# BeatleCalc.net
KiCad netlist of a schematic drawn in EAGLE
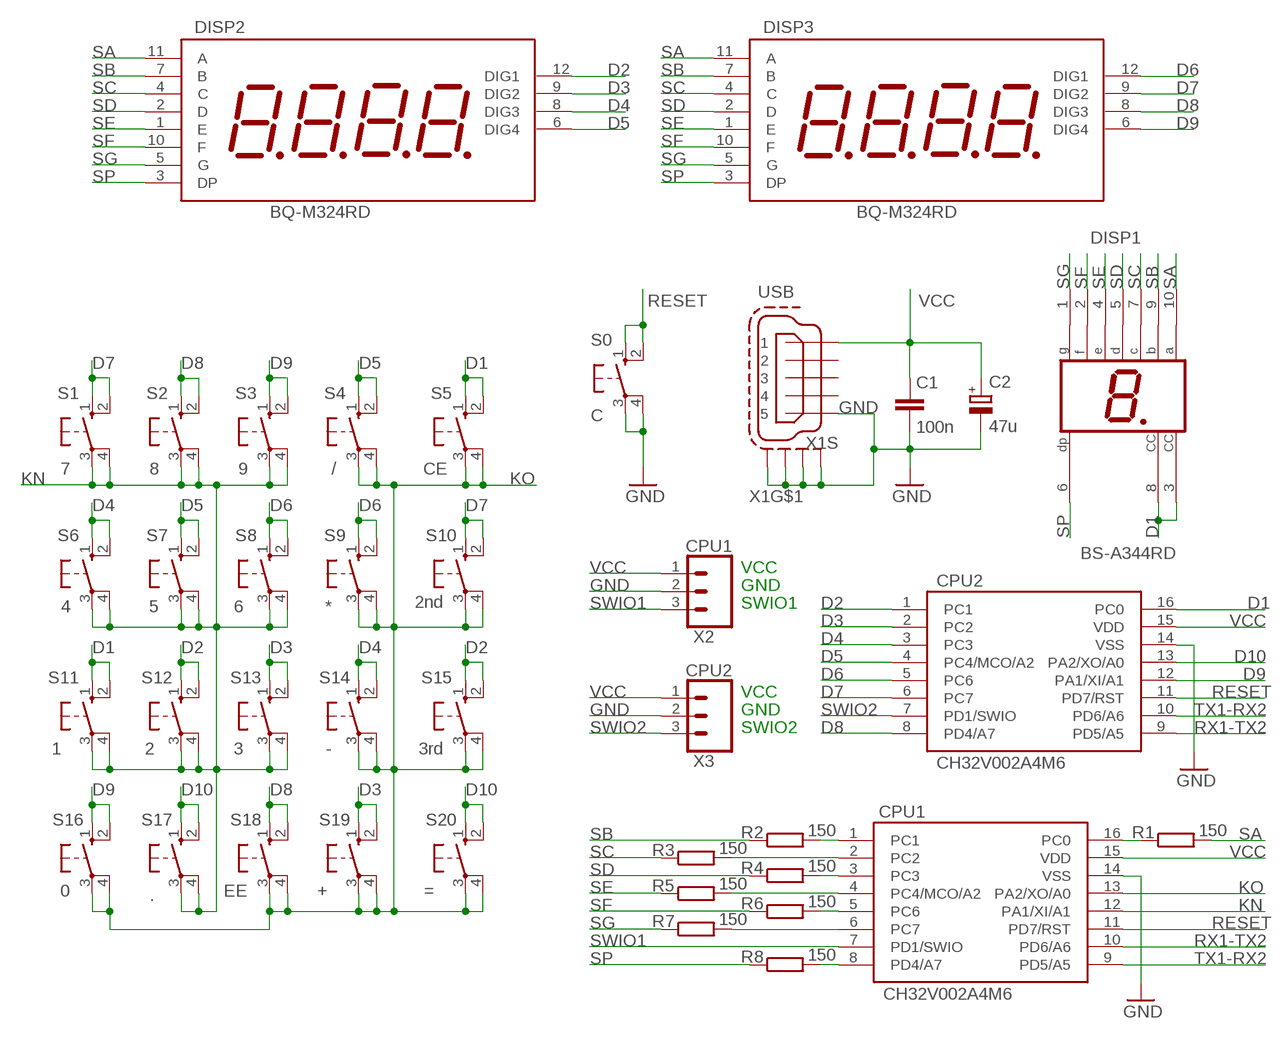
[diagram p0: schematic, sheet 1]

(export (version "E")
  (design (tool "Eeschema 10.0.6"))
  (components
    (comp (ref "C1")
      (value "100n")
      (footprint "eagle-import:C050-024X044")
      (libsource (lib "eagle-import") (part "C-EU050-024X044"))
    )
    (comp (ref "C2")
      (value "47u")
      (footprint "eagle-import:TT2D6L")
      (libsource (lib "eagle-import") (part "CPOL-EUTT2D6L"))
    )
    (comp (ref "CPU1")
      (value "CH32V002A4M6")
      (footprint "eagle-import:SOP16")
      (libsource (lib "eagle-import") (part "CH32V002A4M6"))
    )
    (comp (ref "CPU2")
      (value "CH32V002A4M6")
      (footprint "eagle-import:SOP16")
      (libsource (lib "eagle-import") (part "CH32V002A4M6"))
    )
    (comp (ref "DISP1")
      (value "BS-A344RD")
      (footprint "eagle-import:HDSP-E")
      (libsource (lib "eagle-import") (part "SC39-11SRWA"))
    )
    (comp (ref "DISP2")
      (value "BQ-M324RD")
      (footprint "eagle-import:4DIG_7SEG_92MM")
      (libsource (lib "eagle-import") (part "4DIG_7SEG_92MM"))
    )
    (comp (ref "DISP3")
      (value "BQ-M324RD")
      (footprint "eagle-import:4DIG_7SEG_92MM")
      (libsource (lib "eagle-import") (part "4DIG_7SEG_92MM"))
    )
    (comp (ref "R1")
      (value "150")
      (footprint "eagle-import:0204_10")
      (libsource (lib "eagle-import") (part "R-EU_0204/10"))
    )
    (comp (ref "R2")
      (value "150")
      (footprint "eagle-import:0204_10")
      (libsource (lib "eagle-import") (part "R-EU_0204/10"))
    )
    (comp (ref "R3")
      (value "150")
      (footprint "eagle-import:0204_10")
      (libsource (lib "eagle-import") (part "R-EU_0204/10"))
    )
    (comp (ref "R4")
      (value "150")
      (footprint "eagle-import:0204_10")
      (libsource (lib "eagle-import") (part "R-EU_0204/10"))
    )
    (comp (ref "R5")
      (value "150")
      (footprint "eagle-import:0204_10")
      (libsource (lib "eagle-import") (part "R-EU_0204/10"))
    )
    (comp (ref "R6")
      (value "150")
      (footprint "eagle-import:0204_10")
      (libsource (lib "eagle-import") (part "R-EU_0204/10"))
    )
    (comp (ref "R7")
      (value "150")
      (footprint "eagle-import:0204_10")
      (libsource (lib "eagle-import") (part "R-EU_0204/10"))
    )
    (comp (ref "R8")
      (value "150")
      (footprint "eagle-import:0204_10")
      (libsource (lib "eagle-import") (part "R-EU_0204/10"))
    )
    (comp (ref "S0")
      (value "C")
      (footprint "eagle-import:B3F-10XX")
      (fields (field (name "MPN") "B3F-1000"))
      (libsource (lib "eagle-import") (part "10-XX"))
    )
    (comp (ref "S1")
      (value "7")
      (footprint "eagle-import:B3F-10XX")
      (fields (field (name "MPN") "B3F-1000"))
      (libsource (lib "eagle-import") (part "10-XX"))
    )
    (comp (ref "S2")
      (value "8")
      (footprint "eagle-import:B3F-10XX")
      (fields (field (name "MPN") "B3F-1000"))
      (libsource (lib "eagle-import") (part "10-XX"))
    )
    (comp (ref "S3")
      (value "9")
      (footprint "eagle-import:B3F-10XX")
      (fields (field (name "MPN") "B3F-1000"))
      (libsource (lib "eagle-import") (part "10-XX"))
    )
    (comp (ref "S4")
      (value "/")
      (footprint "eagle-import:B3F-10XX")
      (fields (field (name "MPN") "B3F-1000"))
      (libsource (lib "eagle-import") (part "10-XX"))
    )
    (comp (ref "S5")
      (value "CE")
      (footprint "eagle-import:B3F-10XX")
      (fields (field (name "MPN") "B3F-1000"))
      (libsource (lib "eagle-import") (part "10-XX"))
    )
    (comp (ref "S6")
      (value "4")
      (footprint "eagle-import:B3F-10XX")
      (fields (field (name "MPN") "B3F-1000"))
      (libsource (lib "eagle-import") (part "10-XX"))
    )
    (comp (ref "S7")
      (value "5")
      (footprint "eagle-import:B3F-10XX")
      (fields (field (name "MPN") "B3F-1000"))
      (libsource (lib "eagle-import") (part "10-XX"))
    )
    (comp (ref "S8")
      (value "6")
      (footprint "eagle-import:B3F-10XX")
      (fields (field (name "MPN") "B3F-1000"))
      (libsource (lib "eagle-import") (part "10-XX"))
    )
    (comp (ref "S9")
      (value "*")
      (footprint "eagle-import:B3F-10XX")
      (fields (field (name "MPN") "B3F-1000"))
      (libsource (lib "eagle-import") (part "10-XX"))
    )
    (comp (ref "S10")
      (value "2nd")
      (footprint "eagle-import:B3F-10XX")
      (fields (field (name "MPN") "B3F-1000"))
      (libsource (lib "eagle-import") (part "10-XX"))
    )
    (comp (ref "S11")
      (value "1")
      (footprint "eagle-import:B3F-10XX")
      (fields (field (name "MPN") "B3F-1000"))
      (libsource (lib "eagle-import") (part "10-XX"))
    )
    (comp (ref "S12")
      (value "2")
      (footprint "eagle-import:B3F-10XX")
      (fields (field (name "MPN") "B3F-1000"))
      (libsource (lib "eagle-import") (part "10-XX"))
    )
    (comp (ref "S13")
      (value "3")
      (footprint "eagle-import:B3F-10XX")
      (fields (field (name "MPN") "B3F-1000"))
      (libsource (lib "eagle-import") (part "10-XX"))
    )
    (comp (ref "S14")
      (value "-")
      (footprint "eagle-import:B3F-10XX")
      (fields (field (name "MPN") "B3F-1000"))
      (libsource (lib "eagle-import") (part "10-XX"))
    )
    (comp (ref "S15")
      (value "3rd")
      (footprint "eagle-import:B3F-10XX")
      (fields (field (name "MPN") "B3F-1000"))
      (libsource (lib "eagle-import") (part "10-XX"))
    )
    (comp (ref "S16")
      (value "0")
      (footprint "eagle-import:B3F-10XX")
      (fields (field (name "MPN") "B3F-1000"))
      (libsource (lib "eagle-import") (part "10-XX"))
    )
    (comp (ref "S17")
      (value ".")
      (footprint "eagle-import:B3F-10XX")
      (fields (field (name "MPN") "B3F-1000"))
      (libsource (lib "eagle-import") (part "10-XX"))
    )
    (comp (ref "S18")
      (value "EE")
      (footprint "eagle-import:B3F-10XX")
      (fields (field (name "MPN") "B3F-1000"))
      (libsource (lib "eagle-import") (part "10-XX"))
    )
    (comp (ref "S19")
      (value "+")
      (footprint "eagle-import:B3F-10XX")
      (fields (field (name "MPN") "B3F-1000"))
      (libsource (lib "eagle-import") (part "10-XX"))
    )
    (comp (ref "S20")
      (value "=")
      (footprint "eagle-import:B3F-10XX")
      (fields (field (name "MPN") "B3F-1000"))
      (libsource (lib "eagle-import") (part "10-XX"))
    )
    (comp (ref "X1")
      (value "USB")
      (footprint "eagle-import:32005-201")
      (libsource (lib "eagle-import") (part "MINI-USB-SCHIELD-32005-201"))
    )
    (comp (ref "X2")
      (value "CPU1")
      (footprint "eagle-import:1X03_LONGPADS")
      (libsource (lib "eagle-import") (part "CONN_03LONGPADS"))
    )
    (comp (ref "X3")
      (value "CPU2")
      (footprint "eagle-import:1X03_LONGPADS")
      (libsource (lib "eagle-import") (part "CONN_03LONGPADS"))
    )
  )
  (nets
    (net (code "1") (name "/D1") (class "Default")
      (node (ref "CPU2") (pin "16") (pinfunction "PC0_16") (pintype "bidirectional"))
      (node (ref "DISP1") (pin "3") (pinfunction "CC_3") (pintype "passive"))
      (node (ref "DISP1") (pin "8") (pinfunction "CC_8") (pintype "passive"))
      (node (ref "S11") (pin "1") (pinfunction "S_1") (pintype "passive"))
      (node (ref "S11") (pin "2") (pinfunction "S1_2") (pintype "passive"))
      (node (ref "S5") (pin "1") (pinfunction "S_1") (pintype "passive"))
      (node (ref "S5") (pin "2") (pinfunction "S1_2") (pintype "passive"))
    )
    (net (code "2") (name "/D2") (class "Default")
      (node (ref "CPU2") (pin "1") (pinfunction "PC1_1") (pintype "bidirectional"))
      (node (ref "DISP2") (pin "12") (pinfunction "DIG1_12") (pintype "bidirectional"))
      (node (ref "S12") (pin "1") (pinfunction "S_1") (pintype "passive"))
      (node (ref "S12") (pin "2") (pinfunction "S1_2") (pintype "passive"))
      (node (ref "S15") (pin "1") (pinfunction "S_1") (pintype "passive"))
      (node (ref "S15") (pin "2") (pinfunction "S1_2") (pintype "passive"))
    )
    (net (code "3") (name "/D3") (class "Default")
      (node (ref "CPU2") (pin "2") (pinfunction "PC2_2") (pintype "bidirectional"))
      (node (ref "DISP2") (pin "9") (pinfunction "DIG2_9") (pintype "bidirectional"))
      (node (ref "S13") (pin "1") (pinfunction "S_1") (pintype "passive"))
      (node (ref "S13") (pin "2") (pinfunction "S1_2") (pintype "passive"))
      (node (ref "S19") (pin "1") (pinfunction "S_1") (pintype "passive"))
      (node (ref "S19") (pin "2") (pinfunction "S1_2") (pintype "passive"))
    )
    (net (code "4") (name "/D4") (class "Default")
      (node (ref "CPU2") (pin "3") (pinfunction "PC3_3") (pintype "bidirectional"))
      (node (ref "DISP2") (pin "8") (pinfunction "DIG3_8") (pintype "bidirectional"))
      (node (ref "S14") (pin "1") (pinfunction "S_1") (pintype "passive"))
      (node (ref "S14") (pin "2") (pinfunction "S1_2") (pintype "passive"))
      (node (ref "S6") (pin "1") (pinfunction "S_1") (pintype "passive"))
      (node (ref "S6") (pin "2") (pinfunction "S1_2") (pintype "passive"))
    )
    (net (code "5") (name "/D5") (class "Default")
      (node (ref "CPU2") (pin "4") (pinfunction "PC4/MCO/A2_4") (pintype "bidirectional"))
      (node (ref "DISP2") (pin "6") (pinfunction "DIG4_6") (pintype "bidirectional"))
      (node (ref "S4") (pin "1") (pinfunction "S_1") (pintype "passive"))
      (node (ref "S4") (pin "2") (pinfunction "S1_2") (pintype "passive"))
      (node (ref "S7") (pin "1") (pinfunction "S_1") (pintype "passive"))
      (node (ref "S7") (pin "2") (pinfunction "S1_2") (pintype "passive"))
    )
    (net (code "6") (name "/D6") (class "Default")
      (node (ref "CPU2") (pin "5") (pinfunction "PC6_5") (pintype "bidirectional"))
      (node (ref "DISP3") (pin "12") (pinfunction "DIG1_12") (pintype "bidirectional"))
      (node (ref "S8") (pin "1") (pinfunction "S_1") (pintype "passive"))
      (node (ref "S8") (pin "2") (pinfunction "S1_2") (pintype "passive"))
      (node (ref "S9") (pin "1") (pinfunction "S_1") (pintype "passive"))
      (node (ref "S9") (pin "2") (pinfunction "S1_2") (pintype "passive"))
    )
    (net (code "7") (name "/D7") (class "Default")
      (node (ref "CPU2") (pin "6") (pinfunction "PC7_6") (pintype "bidirectional"))
      (node (ref "DISP3") (pin "9") (pinfunction "DIG2_9") (pintype "bidirectional"))
      (node (ref "S1") (pin "1") (pinfunction "S_1") (pintype "passive"))
      (node (ref "S1") (pin "2") (pinfunction "S1_2") (pintype "passive"))
      (node (ref "S10") (pin "1") (pinfunction "S_1") (pintype "passive"))
      (node (ref "S10") (pin "2") (pinfunction "S1_2") (pintype "passive"))
    )
    (net (code "8") (name "/D8") (class "Default")
      (node (ref "CPU2") (pin "8") (pinfunction "PD4/A7_8") (pintype "bidirectional"))
      (node (ref "DISP3") (pin "8") (pinfunction "DIG3_8") (pintype "bidirectional"))
      (node (ref "S18") (pin "1") (pinfunction "S_1") (pintype "passive"))
      (node (ref "S18") (pin "2") (pinfunction "S1_2") (pintype "passive"))
      (node (ref "S2") (pin "1") (pinfunction "S_1") (pintype "passive"))
      (node (ref "S2") (pin "2") (pinfunction "S1_2") (pintype "passive"))
    )
    (net (code "9") (name "/D9") (class "Default")
      (node (ref "CPU2") (pin "12") (pinfunction "PA1/XI/A1_12") (pintype "bidirectional"))
      (node (ref "DISP3") (pin "6") (pinfunction "DIG4_6") (pintype "bidirectional"))
      (node (ref "S16") (pin "1") (pinfunction "S_1") (pintype "passive"))
      (node (ref "S16") (pin "2") (pinfunction "S1_2") (pintype "passive"))
      (node (ref "S3") (pin "1") (pinfunction "S_1") (pintype "passive"))
      (node (ref "S3") (pin "2") (pinfunction "S1_2") (pintype "passive"))
    )
    (net (code "10") (name "/D10") (class "Default")
      (node (ref "CPU2") (pin "13") (pinfunction "PA2/XO/A0_13") (pintype "bidirectional"))
      (node (ref "S17") (pin "1") (pinfunction "S_1") (pintype "passive"))
      (node (ref "S17") (pin "2") (pinfunction "S1_2") (pintype "passive"))
      (node (ref "S20") (pin "1") (pinfunction "S_1") (pintype "passive"))
      (node (ref "S20") (pin "2") (pinfunction "S1_2") (pintype "passive"))
    )
    (net (code "11") (name "/KN") (class "Default")
      (node (ref "CPU1") (pin "12") (pinfunction "PA1/XI/A1_12") (pintype "bidirectional"))
      (node (ref "S1") (pin "3") (pinfunction "P_3") (pintype "passive"))
      (node (ref "S1") (pin "4") (pinfunction "P1_4") (pintype "passive"))
      (node (ref "S11") (pin "3") (pinfunction "P_3") (pintype "passive"))
      (node (ref "S11") (pin "4") (pinfunction "P1_4") (pintype "passive"))
      (node (ref "S12") (pin "3") (pinfunction "P_3") (pintype "passive"))
      (node (ref "S12") (pin "4") (pinfunction "P1_4") (pintype "passive"))
      (node (ref "S13") (pin "3") (pinfunction "P_3") (pintype "passive"))
      (node (ref "S13") (pin "4") (pinfunction "P1_4") (pintype "passive"))
      (node (ref "S17") (pin "3") (pinfunction "P_3") (pintype "passive"))
      (node (ref "S17") (pin "4") (pinfunction "P1_4") (pintype "passive"))
      (node (ref "S2") (pin "3") (pinfunction "P_3") (pintype "passive"))
      (node (ref "S2") (pin "4") (pinfunction "P1_4") (pintype "passive"))
      (node (ref "S3") (pin "3") (pinfunction "P_3") (pintype "passive"))
      (node (ref "S3") (pin "4") (pinfunction "P1_4") (pintype "passive"))
      (node (ref "S6") (pin "3") (pinfunction "P_3") (pintype "passive"))
      (node (ref "S6") (pin "4") (pinfunction "P1_4") (pintype "passive"))
      (node (ref "S7") (pin "3") (pinfunction "P_3") (pintype "passive"))
      (node (ref "S7") (pin "4") (pinfunction "P1_4") (pintype "passive"))
      (node (ref "S8") (pin "3") (pinfunction "P_3") (pintype "passive"))
      (node (ref "S8") (pin "4") (pinfunction "P1_4") (pintype "passive"))
    )
    (net (code "12") (name "/KO") (class "Default")
      (node (ref "CPU1") (pin "13") (pinfunction "PA2/XO/A0_13") (pintype "bidirectional"))
      (node (ref "S10") (pin "3") (pinfunction "P_3") (pintype "passive"))
      (node (ref "S10") (pin "4") (pinfunction "P1_4") (pintype "passive"))
      (node (ref "S14") (pin "3") (pinfunction "P_3") (pintype "passive"))
      (node (ref "S14") (pin "4") (pinfunction "P1_4") (pintype "passive"))
      (node (ref "S15") (pin "3") (pinfunction "P_3") (pintype "passive"))
      (node (ref "S15") (pin "4") (pinfunction "P1_4") (pintype "passive"))
      (node (ref "S16") (pin "3") (pinfunction "P_3") (pintype "passive"))
      (node (ref "S16") (pin "4") (pinfunction "P1_4") (pintype "passive"))
      (node (ref "S18") (pin "3") (pinfunction "P_3") (pintype "passive"))
      (node (ref "S18") (pin "4") (pinfunction "P1_4") (pintype "passive"))
      (node (ref "S19") (pin "3") (pinfunction "P_3") (pintype "passive"))
      (node (ref "S19") (pin "4") (pinfunction "P1_4") (pintype "passive"))
      (node (ref "S20") (pin "3") (pinfunction "P_3") (pintype "passive"))
      (node (ref "S20") (pin "4") (pinfunction "P1_4") (pintype "passive"))
      (node (ref "S4") (pin "3") (pinfunction "P_3") (pintype "passive"))
      (node (ref "S4") (pin "4") (pinfunction "P1_4") (pintype "passive"))
      (node (ref "S5") (pin "3") (pinfunction "P_3") (pintype "passive"))
      (node (ref "S5") (pin "4") (pinfunction "P1_4") (pintype "passive"))
      (node (ref "S9") (pin "3") (pinfunction "P_3") (pintype "passive"))
      (node (ref "S9") (pin "4") (pinfunction "P1_4") (pintype "passive"))
    )
    (net (code "13") (name "/RESET") (class "Default")
      (node (ref "CPU1") (pin "11") (pinfunction "PD7/RST_11") (pintype "bidirectional"))
      (node (ref "CPU2") (pin "11") (pinfunction "PD7/RST_11") (pintype "bidirectional"))
      (node (ref "S0") (pin "1") (pinfunction "S_1") (pintype "passive"))
      (node (ref "S0") (pin "2") (pinfunction "S1_2") (pintype "passive"))
    )
    (net (code "14") (name "/RX1-TX2") (class "Default")
      (node (ref "CPU1") (pin "10") (pinfunction "PD6/A6_10") (pintype "bidirectional"))
      (node (ref "CPU2") (pin "9") (pinfunction "PD5/A5_9") (pintype "bidirectional"))
    )
    (net (code "15") (name "/SA") (class "Default")
      (node (ref "DISP1") (pin "10") (pinfunction "A_10") (pintype "passive"))
      (node (ref "DISP2") (pin "11") (pinfunction "A_11") (pintype "bidirectional"))
      (node (ref "DISP3") (pin "11") (pinfunction "A_11") (pintype "bidirectional"))
      (node (ref "R1") (pin "2") (pinfunction "2_2") (pintype "passive"))
    )
    (net (code "16") (name "/SB") (class "Default")
      (node (ref "DISP1") (pin "9") (pinfunction "B_9") (pintype "passive"))
      (node (ref "DISP2") (pin "7") (pinfunction "B_7") (pintype "bidirectional"))
      (node (ref "DISP3") (pin "7") (pinfunction "B_7") (pintype "bidirectional"))
      (node (ref "R2") (pin "1") (pinfunction "1_1") (pintype "passive"))
    )
    (net (code "17") (name "/SC") (class "Default")
      (node (ref "DISP1") (pin "7") (pinfunction "C_7") (pintype "passive"))
      (node (ref "DISP2") (pin "4") (pinfunction "C_4") (pintype "bidirectional"))
      (node (ref "DISP3") (pin "4") (pinfunction "C_4") (pintype "bidirectional"))
      (node (ref "R3") (pin "1") (pinfunction "1_1") (pintype "passive"))
    )
    (net (code "18") (name "/SD") (class "Default")
      (node (ref "DISP1") (pin "5") (pinfunction "D_5") (pintype "passive"))
      (node (ref "DISP2") (pin "2") (pinfunction "D_2") (pintype "bidirectional"))
      (node (ref "DISP3") (pin "2") (pinfunction "D_2") (pintype "bidirectional"))
      (node (ref "R4") (pin "1") (pinfunction "1_1") (pintype "passive"))
    )
    (net (code "19") (name "/SE") (class "Default")
      (node (ref "DISP1") (pin "4") (pinfunction "E_4") (pintype "passive"))
      (node (ref "DISP2") (pin "1") (pinfunction "E_1") (pintype "bidirectional"))
      (node (ref "DISP3") (pin "1") (pinfunction "E_1") (pintype "bidirectional"))
      (node (ref "R5") (pin "1") (pinfunction "1_1") (pintype "passive"))
    )
    (net (code "20") (name "/SF") (class "Default")
      (node (ref "DISP1") (pin "2") (pinfunction "F_2") (pintype "passive"))
      (node (ref "DISP2") (pin "10") (pinfunction "F_10") (pintype "bidirectional"))
      (node (ref "DISP3") (pin "10") (pinfunction "F_10") (pintype "bidirectional"))
      (node (ref "R6") (pin "1") (pinfunction "1_1") (pintype "passive"))
    )
    (net (code "21") (name "/SG") (class "Default")
      (node (ref "DISP1") (pin "1") (pinfunction "G_1") (pintype "passive"))
      (node (ref "DISP2") (pin "5") (pinfunction "G_5") (pintype "bidirectional"))
      (node (ref "DISP3") (pin "5") (pinfunction "G_5") (pintype "bidirectional"))
      (node (ref "R7") (pin "1") (pinfunction "1_1") (pintype "passive"))
    )
    (net (code "22") (name "/SP") (class "Default")
      (node (ref "DISP1") (pin "6") (pinfunction "DP_6") (pintype "passive"))
      (node (ref "DISP2") (pin "3") (pinfunction "DP_3") (pintype "bidirectional"))
      (node (ref "DISP3") (pin "3") (pinfunction "DP_3") (pintype "bidirectional"))
      (node (ref "R8") (pin "1") (pinfunction "1_1") (pintype "passive"))
    )
    (net (code "23") (name "/SWIO1") (class "Default")
      (node (ref "CPU1") (pin "7") (pinfunction "PD1/SWIO_7") (pintype "bidirectional"))
      (node (ref "X2") (pin "3") (pinfunction "3_3") (pintype "passive"))
    )
    (net (code "24") (name "/SWIO2") (class "Default")
      (node (ref "CPU2") (pin "7") (pinfunction "PD1/SWIO_7") (pintype "bidirectional"))
      (node (ref "X3") (pin "3") (pinfunction "3_3") (pintype "passive"))
    )
    (net (code "25") (name "/TX1-RX2") (class "Default")
      (node (ref "CPU1") (pin "9") (pinfunction "PD5/A5_9") (pintype "bidirectional"))
      (node (ref "CPU2") (pin "10") (pinfunction "PD6/A6_10") (pintype "bidirectional"))
    )
    (net (code "26") (name "/VCC") (class "Default")
      (node (ref "C1") (pin "1") (pinfunction "1_1") (pintype "passive"))
      (node (ref "C2") (pin "+") (pinfunction "+_+") (pintype "passive"))
      (node (ref "CPU1") (pin "15") (pinfunction "VDD_15") (pintype "power_in"))
      (node (ref "CPU2") (pin "15") (pinfunction "VDD_15") (pintype "power_in"))
      (node (ref "X1") (pin "1") (pinfunction "1_1") (pintype "passive"))
      (node (ref "X2") (pin "1") (pinfunction "1_1") (pintype "passive"))
      (node (ref "X3") (pin "1") (pinfunction "1_1") (pintype "passive"))
    )
    (net (code "27") (name "GND") (class "Default")
      (node (ref "C1") (pin "2") (pinfunction "2_2") (pintype "passive"))
      (node (ref "C2") (pin "-") (pinfunction "-_-") (pintype "passive"))
      (node (ref "CPU1") (pin "14") (pinfunction "VSS_14") (pintype "power_in"))
      (node (ref "CPU2") (pin "14") (pinfunction "VSS_14") (pintype "power_in"))
      (node (ref "S0") (pin "3") (pinfunction "P_3") (pintype "passive"))
      (node (ref "S0") (pin "4") (pinfunction "P1_4") (pintype "passive"))
      (node (ref "X1") (pin "5") (pinfunction "5_5") (pintype "passive"))
      (node (ref "X1") (pin "M1") (pinfunction "S1_M1") (pintype "passive"))
      (node (ref "X1") (pin "M2") (pinfunction "S2_M2") (pintype "passive"))
      (node (ref "X1") (pin "M3") (pinfunction "S3_M3") (pintype "passive"))
      (node (ref "X1") (pin "M4") (pinfunction "S4_M4") (pintype "passive"))
      (node (ref "X2") (pin "2") (pinfunction "2_2") (pintype "passive"))
      (node (ref "X3") (pin "2") (pinfunction "2_2") (pintype "passive"))
    )
    (net (code "28") (name "Net-(CPU1-PC0)") (class "Default")
      (node (ref "CPU1") (pin "16") (pinfunction "PC0_16") (pintype "bidirectional"))
      (node (ref "R1") (pin "1") (pinfunction "1_1") (pintype "passive"))
    )
    (net (code "29") (name "Net-(CPU1-PC1)") (class "Default")
      (node (ref "CPU1") (pin "1") (pinfunction "PC1_1") (pintype "bidirectional"))
      (node (ref "R2") (pin "2") (pinfunction "2_2") (pintype "passive"))
    )
    (net (code "30") (name "Net-(CPU1-PC2)") (class "Default")
      (node (ref "CPU1") (pin "2") (pinfunction "PC2_2") (pintype "bidirectional"))
      (node (ref "R3") (pin "2") (pinfunction "2_2") (pintype "passive"))
    )
    (net (code "31") (name "Net-(CPU1-PC3)") (class "Default")
      (node (ref "CPU1") (pin "3") (pinfunction "PC3_3") (pintype "bidirectional"))
      (node (ref "R4") (pin "2") (pinfunction "2_2") (pintype "passive"))
    )
    (net (code "32") (name "Net-(CPU1-PC4{slash}MCO{slash}A2)") (class "Default")
      (node (ref "CPU1") (pin "4") (pinfunction "PC4/MCO/A2_4") (pintype "bidirectional"))
      (node (ref "R5") (pin "2") (pinfunction "2_2") (pintype "passive"))
    )
    (net (code "33") (name "Net-(CPU1-PC6)") (class "Default")
      (node (ref "CPU1") (pin "5") (pinfunction "PC6_5") (pintype "bidirectional"))
      (node (ref "R6") (pin "2") (pinfunction "2_2") (pintype "passive"))
    )
    (net (code "34") (name "Net-(CPU1-PC7)") (class "Default")
      (node (ref "CPU1") (pin "6") (pinfunction "PC7_6") (pintype "bidirectional"))
      (node (ref "R7") (pin "2") (pinfunction "2_2") (pintype "passive"))
    )
    (net (code "35") (name "Net-(CPU1-PD4{slash}A7)") (class "Default")
      (node (ref "CPU1") (pin "8") (pinfunction "PD4/A7_8") (pintype "bidirectional"))
      (node (ref "R8") (pin "2") (pinfunction "2_2") (pintype "passive"))
    )
    (net (code "36") (name "unconnected-(X1-Pad2)") (class "Default")
      (node (ref "X1") (pin "2") (pinfunction "2_2") (pintype "passive"))
    )
    (net (code "37") (name "unconnected-(X1-Pad3)") (class "Default")
      (node (ref "X1") (pin "3") (pinfunction "3_3") (pintype "passive"))
    )
    (net (code "38") (name "unconnected-(X1-Pad4)") (class "Default")
      (node (ref "X1") (pin "4") (pinfunction "4_4") (pintype "passive"))
    )
  )
)
